# kb2040_pocketOperator_out_revA.net
KiCad netlist of a schematic drawn in EAGLE
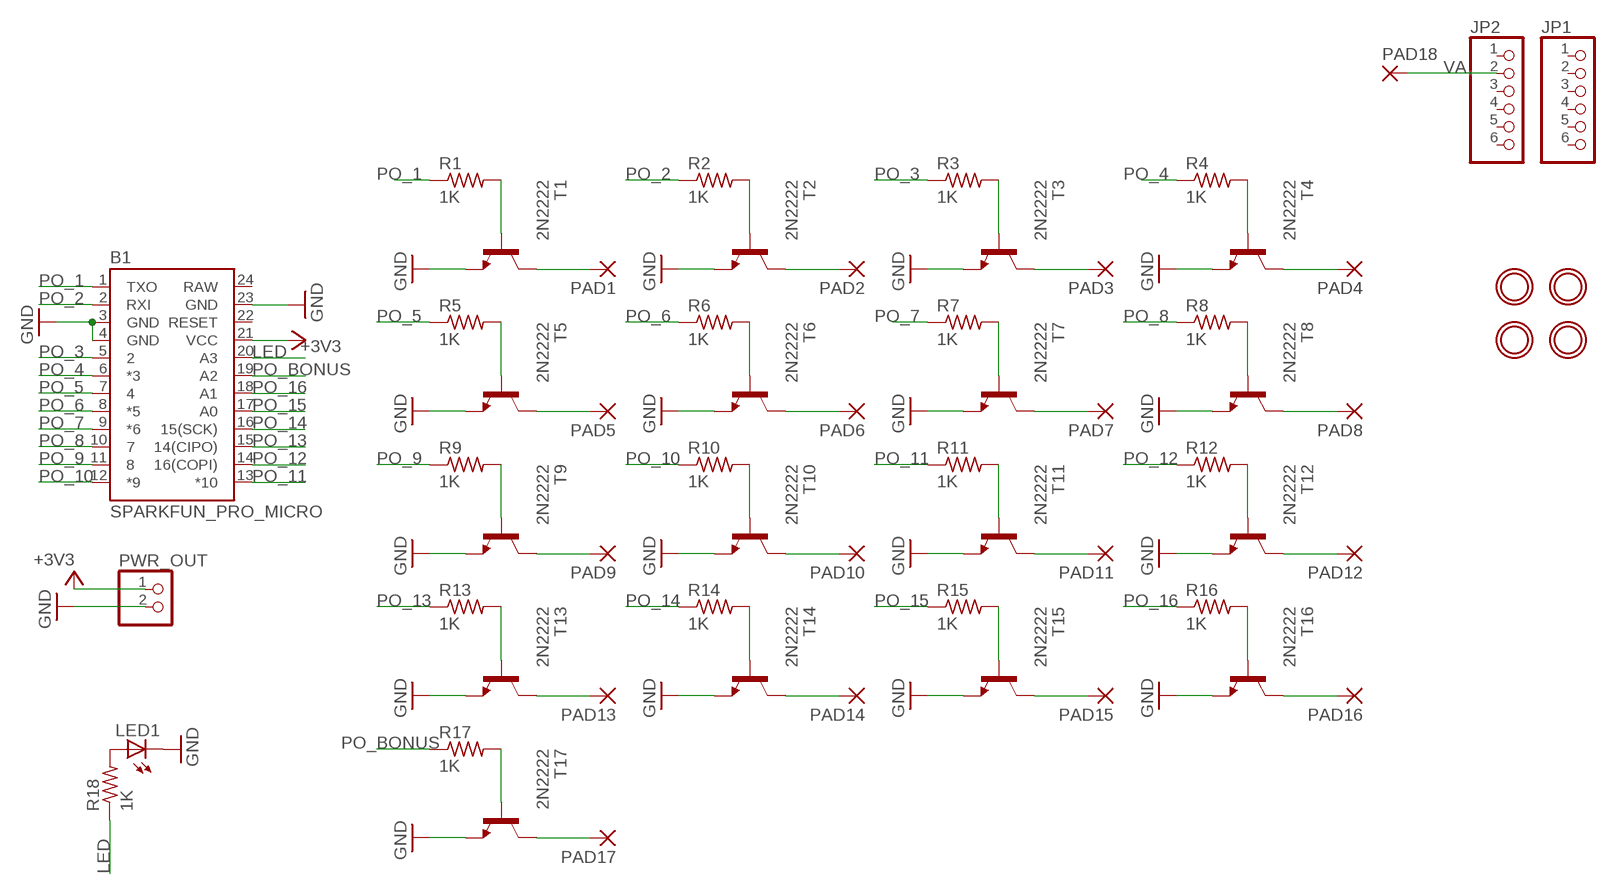
[diagram p0: schematic, sheet 1]

(export (version "E")
  (design (tool "Eeschema 10.0.6"))
  (components
    (comp (ref "B1")
      (value "SPARKFUN_PRO_MICRO")
      (footprint "eagle-import:SPARKFUN_PRO_MICRO")
      (libsource (lib "eagle-import") (part "SPARKFUN_PRO_MICRO"))
    )
    (comp (ref "JP1")
      (value "HEADER-1X670MIL")
      (footprint "eagle-import:1X06_ROUND_70")
      (libsource (lib "eagle-import") (part "HEADER-1X670MIL"))
    )
    (comp (ref "JP2")
      (value "HEADER-1X670MIL")
      (footprint "eagle-import:1X06_ROUND_70")
      (libsource (lib "eagle-import") (part "HEADER-1X670MIL"))
    )
    (comp (ref "LED1")
      (value "LED5MM")
      (footprint "eagle-import:LED5MM")
      (libsource (lib "eagle-import") (part "LED5MM"))
    )
    (comp (ref "PAD1")
      (value "2,54/1,1")
      (footprint "eagle-import:2,54_1,1")
      (libsource (lib "eagle-import") (part "2,54/1,1"))
    )
    (comp (ref "PAD2")
      (value "2,54/1,1")
      (footprint "eagle-import:2,54_1,1")
      (libsource (lib "eagle-import") (part "2,54/1,1"))
    )
    (comp (ref "PAD3")
      (value "2,54/1,1")
      (footprint "eagle-import:2,54_1,1")
      (libsource (lib "eagle-import") (part "2,54/1,1"))
    )
    (comp (ref "PAD4")
      (value "2,54/1,1")
      (footprint "eagle-import:2,54_1,1")
      (libsource (lib "eagle-import") (part "2,54/1,1"))
    )
    (comp (ref "PAD5")
      (value "2,54/1,1")
      (footprint "eagle-import:2,54_1,1")
      (libsource (lib "eagle-import") (part "2,54/1,1"))
    )
    (comp (ref "PAD6")
      (value "2,54/1,1")
      (footprint "eagle-import:2,54_1,1")
      (libsource (lib "eagle-import") (part "2,54/1,1"))
    )
    (comp (ref "PAD7")
      (value "2,54/1,1")
      (footprint "eagle-import:2,54_1,1")
      (libsource (lib "eagle-import") (part "2,54/1,1"))
    )
    (comp (ref "PAD8")
      (value "2,54/1,1")
      (footprint "eagle-import:2,54_1,1")
      (libsource (lib "eagle-import") (part "2,54/1,1"))
    )
    (comp (ref "PAD9")
      (value "2,54/1,1")
      (footprint "eagle-import:2,54_1,1")
      (libsource (lib "eagle-import") (part "2,54/1,1"))
    )
    (comp (ref "PAD10")
      (value "2,54/1,1")
      (footprint "eagle-import:2,54_1,1")
      (libsource (lib "eagle-import") (part "2,54/1,1"))
    )
    (comp (ref "PAD11")
      (value "2,54/1,1")
      (footprint "eagle-import:2,54_1,1")
      (libsource (lib "eagle-import") (part "2,54/1,1"))
    )
    (comp (ref "PAD12")
      (value "2,54/1,1")
      (footprint "eagle-import:2,54_1,1")
      (libsource (lib "eagle-import") (part "2,54/1,1"))
    )
    (comp (ref "PAD13")
      (value "2,54/1,1")
      (footprint "eagle-import:2,54_1,1")
      (libsource (lib "eagle-import") (part "2,54/1,1"))
    )
    (comp (ref "PAD14")
      (value "2,54/1,1")
      (footprint "eagle-import:2,54_1,1")
      (libsource (lib "eagle-import") (part "2,54/1,1"))
    )
    (comp (ref "PAD15")
      (value "2,54/1,1")
      (footprint "eagle-import:2,54_1,1")
      (libsource (lib "eagle-import") (part "2,54/1,1"))
    )
    (comp (ref "PAD16")
      (value "2,54/1,1")
      (footprint "eagle-import:2,54_1,1")
      (libsource (lib "eagle-import") (part "2,54/1,1"))
    )
    (comp (ref "PAD17")
      (value "2,54/1,1")
      (footprint "eagle-import:2,54_1,1")
      (libsource (lib "eagle-import") (part "2,54/1,1"))
    )
    (comp (ref "PAD18")
      (value "2,54/1,1")
      (footprint "eagle-import:2,54_1,1")
      (libsource (lib "eagle-import") (part "2,54/1,1"))
    )
    (comp (ref "PWR_OUT")
      (value "PINHD-1X2")
      (footprint "eagle-import:1X02")
      (libsource (lib "eagle-import") (part "PINHD-1X2"))
    )
    (comp (ref "R1")
      (value "1K")
      (footprint "eagle-import:0414V")
      (libsource (lib "eagle-import") (part "R-US_0414/5V"))
    )
    (comp (ref "R2")
      (value "1K")
      (footprint "eagle-import:0414V")
      (libsource (lib "eagle-import") (part "R-US_0414/5V"))
    )
    (comp (ref "R3")
      (value "1K")
      (footprint "eagle-import:0414V")
      (libsource (lib "eagle-import") (part "R-US_0414/5V"))
    )
    (comp (ref "R4")
      (value "1K")
      (footprint "eagle-import:0414V")
      (libsource (lib "eagle-import") (part "R-US_0414/5V"))
    )
    (comp (ref "R5")
      (value "1K")
      (footprint "eagle-import:0414V")
      (libsource (lib "eagle-import") (part "R-US_0414/5V"))
    )
    (comp (ref "R6")
      (value "1K")
      (footprint "eagle-import:0414V")
      (libsource (lib "eagle-import") (part "R-US_0414/5V"))
    )
    (comp (ref "R7")
      (value "1K")
      (footprint "eagle-import:0414V")
      (libsource (lib "eagle-import") (part "R-US_0414/5V"))
    )
    (comp (ref "R8")
      (value "1K")
      (footprint "eagle-import:0414V")
      (libsource (lib "eagle-import") (part "R-US_0414/5V"))
    )
    (comp (ref "R9")
      (value "1K")
      (footprint "eagle-import:0414V")
      (libsource (lib "eagle-import") (part "R-US_0414/5V"))
    )
    (comp (ref "R10")
      (value "1K")
      (footprint "eagle-import:0414V")
      (libsource (lib "eagle-import") (part "R-US_0414/5V"))
    )
    (comp (ref "R11")
      (value "1K")
      (footprint "eagle-import:0414V")
      (libsource (lib "eagle-import") (part "R-US_0414/5V"))
    )
    (comp (ref "R12")
      (value "1K")
      (footprint "eagle-import:0414V")
      (libsource (lib "eagle-import") (part "R-US_0414/5V"))
    )
    (comp (ref "R13")
      (value "1K")
      (footprint "eagle-import:0414V")
      (libsource (lib "eagle-import") (part "R-US_0414/5V"))
    )
    (comp (ref "R14")
      (value "1K")
      (footprint "eagle-import:0414V")
      (libsource (lib "eagle-import") (part "R-US_0414/5V"))
    )
    (comp (ref "R15")
      (value "1K")
      (footprint "eagle-import:0414V")
      (libsource (lib "eagle-import") (part "R-US_0414/5V"))
    )
    (comp (ref "R16")
      (value "1K")
      (footprint "eagle-import:0414V")
      (libsource (lib "eagle-import") (part "R-US_0414/5V"))
    )
    (comp (ref "R17")
      (value "1K")
      (footprint "eagle-import:0414V")
      (libsource (lib "eagle-import") (part "R-US_0414/5V"))
    )
    (comp (ref "R18")
      (value "1K")
      (footprint "eagle-import:0414V")
      (libsource (lib "eagle-import") (part "R-US_0414/5V"))
    )
    (comp (ref "T1")
      (value "2N2222")
      (footprint "eagle-import:TO92-EBC-OVAL")
      (libsource (lib "eagle-import") (part "2N2222"))
    )
    (comp (ref "T2")
      (value "2N2222")
      (footprint "eagle-import:TO92-EBC-OVAL")
      (libsource (lib "eagle-import") (part "2N2222"))
    )
    (comp (ref "T3")
      (value "2N2222")
      (footprint "eagle-import:TO92-EBC-OVAL")
      (libsource (lib "eagle-import") (part "2N2222"))
    )
    (comp (ref "T4")
      (value "2N2222")
      (footprint "eagle-import:TO92-EBC-OVAL")
      (libsource (lib "eagle-import") (part "2N2222"))
    )
    (comp (ref "T5")
      (value "2N2222")
      (footprint "eagle-import:TO92-EBC-OVAL")
      (libsource (lib "eagle-import") (part "2N2222"))
    )
    (comp (ref "T6")
      (value "2N2222")
      (footprint "eagle-import:TO92-EBC-OVAL")
      (libsource (lib "eagle-import") (part "2N2222"))
    )
    (comp (ref "T7")
      (value "2N2222")
      (footprint "eagle-import:TO92-EBC-OVAL")
      (libsource (lib "eagle-import") (part "2N2222"))
    )
    (comp (ref "T8")
      (value "2N2222")
      (footprint "eagle-import:TO92-EBC-OVAL")
      (libsource (lib "eagle-import") (part "2N2222"))
    )
    (comp (ref "T9")
      (value "2N2222")
      (footprint "eagle-import:TO92-EBC-OVAL")
      (libsource (lib "eagle-import") (part "2N2222"))
    )
    (comp (ref "T10")
      (value "2N2222")
      (footprint "eagle-import:TO92-EBC-OVAL")
      (libsource (lib "eagle-import") (part "2N2222"))
    )
    (comp (ref "T11")
      (value "2N2222")
      (footprint "eagle-import:TO92-EBC-OVAL")
      (libsource (lib "eagle-import") (part "2N2222"))
    )
    (comp (ref "T12")
      (value "2N2222")
      (footprint "eagle-import:TO92-EBC-OVAL")
      (libsource (lib "eagle-import") (part "2N2222"))
    )
    (comp (ref "T13")
      (value "2N2222")
      (footprint "eagle-import:TO92-EBC-OVAL")
      (libsource (lib "eagle-import") (part "2N2222"))
    )
    (comp (ref "T14")
      (value "2N2222")
      (footprint "eagle-import:TO92-EBC-OVAL")
      (libsource (lib "eagle-import") (part "2N2222"))
    )
    (comp (ref "T15")
      (value "2N2222")
      (footprint "eagle-import:TO92-EBC-OVAL")
      (libsource (lib "eagle-import") (part "2N2222"))
    )
    (comp (ref "T16")
      (value "2N2222")
      (footprint "eagle-import:TO92-EBC-OVAL")
      (libsource (lib "eagle-import") (part "2N2222"))
    )
    (comp (ref "T17")
      (value "2N2222")
      (footprint "eagle-import:TO92-EBC-OVAL")
      (libsource (lib "eagle-import") (part "2N2222"))
    )
    (comp (ref "U$1")
      (value "MOUNTINGHOLE2.5")
      (footprint "eagle-import:MOUNTINGHOLE_2.5_PLATED")
      (libsource (lib "eagle-import") (part "MOUNTINGHOLE2.5"))
    )
    (comp (ref "U$17")
      (value "MOUNTINGHOLE2.5")
      (footprint "eagle-import:MOUNTINGHOLE_2.5_PLATED")
      (libsource (lib "eagle-import") (part "MOUNTINGHOLE2.5"))
    )
    (comp (ref "U$19")
      (value "MOUNTINGHOLE2.5")
      (footprint "eagle-import:MOUNTINGHOLE_2.5_PLATED")
      (libsource (lib "eagle-import") (part "MOUNTINGHOLE2.5"))
    )
    (comp (ref "U$21")
      (value "MOUNTINGHOLE2.5")
      (footprint "eagle-import:MOUNTINGHOLE_2.5_PLATED")
      (libsource (lib "eagle-import") (part "MOUNTINGHOLE2.5"))
    )
  )
  (nets
    (net (code "1") (name "+3V3") (class "Default")
      (node (ref "B1") (pin "21") (pinfunction "VCC_21") (pintype "power_in"))
      (node (ref "PWR_OUT") (pin "1") (pinfunction "1_1") (pintype "passive"))
    )
    (net (code "2") (name "/LED") (class "Default")
      (node (ref "B1") (pin "20") (pinfunction "A3_20") (pintype "bidirectional"))
      (node (ref "R18") (pin "1") (pinfunction "1_1") (pintype "passive"))
    )
    (net (code "3") (name "/PO_1") (class "Default")
      (node (ref "B1") (pin "1") (pinfunction "TXO_1") (pintype "bidirectional"))
      (node (ref "R1") (pin "1") (pinfunction "1_1") (pintype "passive"))
    )
    (net (code "4") (name "/PO_2") (class "Default")
      (node (ref "B1") (pin "2") (pinfunction "RXI_2") (pintype "bidirectional"))
      (node (ref "R2") (pin "1") (pinfunction "1_1") (pintype "passive"))
    )
    (net (code "5") (name "/PO_3") (class "Default")
      (node (ref "B1") (pin "5") (pinfunction "2_5") (pintype "bidirectional"))
      (node (ref "R3") (pin "1") (pinfunction "1_1") (pintype "passive"))
    )
    (net (code "6") (name "/PO_4") (class "Default")
      (node (ref "B1") (pin "6") (pinfunction "*3_6") (pintype "bidirectional"))
      (node (ref "R4") (pin "1") (pinfunction "1_1") (pintype "passive"))
    )
    (net (code "7") (name "/PO_5") (class "Default")
      (node (ref "B1") (pin "7") (pinfunction "4_7") (pintype "bidirectional"))
      (node (ref "R5") (pin "1") (pinfunction "1_1") (pintype "passive"))
    )
    (net (code "8") (name "/PO_6") (class "Default")
      (node (ref "B1") (pin "8") (pinfunction "*5_8") (pintype "bidirectional"))
      (node (ref "R6") (pin "1") (pinfunction "1_1") (pintype "passive"))
    )
    (net (code "9") (name "/PO_7") (class "Default")
      (node (ref "B1") (pin "9") (pinfunction "*6_9") (pintype "bidirectional"))
      (node (ref "R7") (pin "1") (pinfunction "1_1") (pintype "passive"))
    )
    (net (code "10") (name "/PO_8") (class "Default")
      (node (ref "B1") (pin "10") (pinfunction "7_10") (pintype "bidirectional"))
      (node (ref "R8") (pin "1") (pinfunction "1_1") (pintype "passive"))
    )
    (net (code "11") (name "/PO_9") (class "Default")
      (node (ref "B1") (pin "11") (pinfunction "8_11") (pintype "bidirectional"))
      (node (ref "R9") (pin "1") (pinfunction "1_1") (pintype "passive"))
    )
    (net (code "12") (name "/PO_10") (class "Default")
      (node (ref "B1") (pin "12") (pinfunction "*9_12") (pintype "bidirectional"))
      (node (ref "R10") (pin "1") (pinfunction "1_1") (pintype "passive"))
    )
    (net (code "13") (name "/PO_11") (class "Default")
      (node (ref "B1") (pin "13") (pinfunction "*10_13") (pintype "bidirectional"))
      (node (ref "R11") (pin "1") (pinfunction "1_1") (pintype "passive"))
    )
    (net (code "14") (name "/PO_12") (class "Default")
      (node (ref "B1") (pin "14") (pinfunction "16(COPI)_14") (pintype "bidirectional"))
      (node (ref "R12") (pin "1") (pinfunction "1_1") (pintype "passive"))
    )
    (net (code "15") (name "/PO_13") (class "Default")
      (node (ref "B1") (pin "15") (pinfunction "14(CIPO)_15") (pintype "bidirectional"))
      (node (ref "R13") (pin "1") (pinfunction "1_1") (pintype "passive"))
    )
    (net (code "16") (name "/PO_14") (class "Default")
      (node (ref "B1") (pin "16") (pinfunction "15(SCK)_16") (pintype "bidirectional"))
      (node (ref "R14") (pin "1") (pinfunction "1_1") (pintype "passive"))
    )
    (net (code "17") (name "/PO_15") (class "Default")
      (node (ref "B1") (pin "17") (pinfunction "A0_17") (pintype "bidirectional"))
      (node (ref "R15") (pin "1") (pinfunction "1_1") (pintype "passive"))
    )
    (net (code "18") (name "/PO_16") (class "Default")
      (node (ref "B1") (pin "18") (pinfunction "A1_18") (pintype "bidirectional"))
      (node (ref "R16") (pin "1") (pinfunction "1_1") (pintype "passive"))
    )
    (net (code "19") (name "/PO_BONUS") (class "Default")
      (node (ref "B1") (pin "19") (pinfunction "A2_19") (pintype "bidirectional"))
      (node (ref "R17") (pin "1") (pinfunction "1_1") (pintype "passive"))
    )
    (net (code "20") (name "/RAW") (class "Default")
      (node (ref "B1") (pin "24") (pinfunction "RAW_24") (pintype "power_in"))
    )
    (net (code "21") (name "/VA") (class "Default")
      (node (ref "JP2") (pin "2") (pinfunction "2_2") (pintype "passive"))
      (node (ref "PAD18") (pin "1") (pinfunction "P_1") (pintype "passive"))
    )
    (net (code "22") (name "GND") (class "Default")
      (node (ref "B1") (pin "23") (pinfunction "GND_23") (pintype "power_in"))
      (node (ref "B1") (pin "3") (pinfunction "GND_3") (pintype "power_in"))
      (node (ref "B1") (pin "4") (pinfunction "GND_4") (pintype "power_in"))
      (node (ref "LED1") (pin "K") (pinfunction "C_K") (pintype "passive"))
      (node (ref "PWR_OUT") (pin "2") (pinfunction "2_2") (pintype "passive"))
      (node (ref "T1") (pin "E") (pinfunction "E_E") (pintype "passive"))
      (node (ref "T10") (pin "E") (pinfunction "E_E") (pintype "passive"))
      (node (ref "T11") (pin "E") (pinfunction "E_E") (pintype "passive"))
      (node (ref "T12") (pin "E") (pinfunction "E_E") (pintype "passive"))
      (node (ref "T13") (pin "E") (pinfunction "E_E") (pintype "passive"))
      (node (ref "T14") (pin "E") (pinfunction "E_E") (pintype "passive"))
      (node (ref "T15") (pin "E") (pinfunction "E_E") (pintype "passive"))
      (node (ref "T16") (pin "E") (pinfunction "E_E") (pintype "passive"))
      (node (ref "T17") (pin "E") (pinfunction "E_E") (pintype "passive"))
      (node (ref "T2") (pin "E") (pinfunction "E_E") (pintype "passive"))
      (node (ref "T3") (pin "E") (pinfunction "E_E") (pintype "passive"))
      (node (ref "T4") (pin "E") (pinfunction "E_E") (pintype "passive"))
      (node (ref "T5") (pin "E") (pinfunction "E_E") (pintype "passive"))
      (node (ref "T6") (pin "E") (pinfunction "E_E") (pintype "passive"))
      (node (ref "T7") (pin "E") (pinfunction "E_E") (pintype "passive"))
      (node (ref "T8") (pin "E") (pinfunction "E_E") (pintype "passive"))
      (node (ref "T9") (pin "E") (pinfunction "E_E") (pintype "passive"))
    )
    (net (code "23") (name "Net-(LED1-PadA)") (class "Default")
      (node (ref "LED1") (pin "A") (pinfunction "A_A") (pintype "passive"))
      (node (ref "R18") (pin "2") (pinfunction "2_2") (pintype "passive"))
    )
    (net (code "24") (name "Net-(PAD1-P)") (class "Default")
      (node (ref "PAD1") (pin "1") (pinfunction "P_1") (pintype "passive"))
      (node (ref "T1") (pin "C") (pinfunction "C_C") (pintype "passive"))
    )
    (net (code "25") (name "Net-(PAD2-P)") (class "Default")
      (node (ref "PAD2") (pin "1") (pinfunction "P_1") (pintype "passive"))
      (node (ref "T2") (pin "C") (pinfunction "C_C") (pintype "passive"))
    )
    (net (code "26") (name "Net-(PAD3-P)") (class "Default")
      (node (ref "PAD3") (pin "1") (pinfunction "P_1") (pintype "passive"))
      (node (ref "T3") (pin "C") (pinfunction "C_C") (pintype "passive"))
    )
    (net (code "27") (name "Net-(PAD4-P)") (class "Default")
      (node (ref "PAD4") (pin "1") (pinfunction "P_1") (pintype "passive"))
      (node (ref "T4") (pin "C") (pinfunction "C_C") (pintype "passive"))
    )
    (net (code "28") (name "Net-(PAD5-P)") (class "Default")
      (node (ref "PAD5") (pin "1") (pinfunction "P_1") (pintype "passive"))
      (node (ref "T5") (pin "C") (pinfunction "C_C") (pintype "passive"))
    )
    (net (code "29") (name "Net-(PAD6-P)") (class "Default")
      (node (ref "PAD6") (pin "1") (pinfunction "P_1") (pintype "passive"))
      (node (ref "T6") (pin "C") (pinfunction "C_C") (pintype "passive"))
    )
    (net (code "30") (name "Net-(PAD7-P)") (class "Default")
      (node (ref "PAD7") (pin "1") (pinfunction "P_1") (pintype "passive"))
      (node (ref "T7") (pin "C") (pinfunction "C_C") (pintype "passive"))
    )
    (net (code "31") (name "Net-(PAD8-P)") (class "Default")
      (node (ref "PAD8") (pin "1") (pinfunction "P_1") (pintype "passive"))
      (node (ref "T8") (pin "C") (pinfunction "C_C") (pintype "passive"))
    )
    (net (code "32") (name "Net-(PAD9-P)") (class "Default")
      (node (ref "PAD9") (pin "1") (pinfunction "P_1") (pintype "passive"))
      (node (ref "T9") (pin "C") (pinfunction "C_C") (pintype "passive"))
    )
    (net (code "33") (name "Net-(PAD10-P)") (class "Default")
      (node (ref "PAD10") (pin "1") (pinfunction "P_1") (pintype "passive"))
      (node (ref "T10") (pin "C") (pinfunction "C_C") (pintype "passive"))
    )
    (net (code "34") (name "Net-(PAD11-P)") (class "Default")
      (node (ref "PAD11") (pin "1") (pinfunction "P_1") (pintype "passive"))
      (node (ref "T11") (pin "C") (pinfunction "C_C") (pintype "passive"))
    )
    (net (code "35") (name "Net-(PAD12-P)") (class "Default")
      (node (ref "PAD12") (pin "1") (pinfunction "P_1") (pintype "passive"))
      (node (ref "T12") (pin "C") (pinfunction "C_C") (pintype "passive"))
    )
    (net (code "36") (name "Net-(PAD13-P)") (class "Default")
      (node (ref "PAD13") (pin "1") (pinfunction "P_1") (pintype "passive"))
      (node (ref "T13") (pin "C") (pinfunction "C_C") (pintype "passive"))
    )
    (net (code "37") (name "Net-(PAD14-P)") (class "Default")
      (node (ref "PAD14") (pin "1") (pinfunction "P_1") (pintype "passive"))
      (node (ref "T14") (pin "C") (pinfunction "C_C") (pintype "passive"))
    )
    (net (code "38") (name "Net-(PAD15-P)") (class "Default")
      (node (ref "PAD15") (pin "1") (pinfunction "P_1") (pintype "passive"))
      (node (ref "T15") (pin "C") (pinfunction "C_C") (pintype "passive"))
    )
    (net (code "39") (name "Net-(PAD16-P)") (class "Default")
      (node (ref "PAD16") (pin "1") (pinfunction "P_1") (pintype "passive"))
      (node (ref "T16") (pin "C") (pinfunction "C_C") (pintype "passive"))
    )
    (net (code "40") (name "Net-(PAD17-P)") (class "Default")
      (node (ref "PAD17") (pin "1") (pinfunction "P_1") (pintype "passive"))
      (node (ref "T17") (pin "C") (pinfunction "C_C") (pintype "passive"))
    )
    (net (code "41") (name "Net-(R1-Pad2)") (class "Default")
      (node (ref "R1") (pin "2") (pinfunction "2_2") (pintype "passive"))
      (node (ref "T1") (pin "B") (pinfunction "B_B") (pintype "passive"))
    )
    (net (code "42") (name "Net-(R2-Pad2)") (class "Default")
      (node (ref "R2") (pin "2") (pinfunction "2_2") (pintype "passive"))
      (node (ref "T2") (pin "B") (pinfunction "B_B") (pintype "passive"))
    )
    (net (code "43") (name "Net-(R3-Pad2)") (class "Default")
      (node (ref "R3") (pin "2") (pinfunction "2_2") (pintype "passive"))
      (node (ref "T3") (pin "B") (pinfunction "B_B") (pintype "passive"))
    )
    (net (code "44") (name "Net-(R4-Pad2)") (class "Default")
      (node (ref "R4") (pin "2") (pinfunction "2_2") (pintype "passive"))
      (node (ref "T4") (pin "B") (pinfunction "B_B") (pintype "passive"))
    )
    (net (code "45") (name "Net-(R5-Pad2)") (class "Default")
      (node (ref "R5") (pin "2") (pinfunction "2_2") (pintype "passive"))
      (node (ref "T5") (pin "B") (pinfunction "B_B") (pintype "passive"))
    )
    (net (code "46") (name "Net-(R6-Pad2)") (class "Default")
      (node (ref "R6") (pin "2") (pinfunction "2_2") (pintype "passive"))
      (node (ref "T6") (pin "B") (pinfunction "B_B") (pintype "passive"))
    )
    (net (code "47") (name "Net-(R7-Pad2)") (class "Default")
      (node (ref "R7") (pin "2") (pinfunction "2_2") (pintype "passive"))
      (node (ref "T7") (pin "B") (pinfunction "B_B") (pintype "passive"))
    )
    (net (code "48") (name "Net-(R8-Pad2)") (class "Default")
      (node (ref "R8") (pin "2") (pinfunction "2_2") (pintype "passive"))
      (node (ref "T8") (pin "B") (pinfunction "B_B") (pintype "passive"))
    )
    (net (code "49") (name "Net-(R9-Pad2)") (class "Default")
      (node (ref "R9") (pin "2") (pinfunction "2_2") (pintype "passive"))
      (node (ref "T9") (pin "B") (pinfunction "B_B") (pintype "passive"))
    )
    (net (code "50") (name "Net-(R10-Pad2)") (class "Default")
      (node (ref "R10") (pin "2") (pinfunction "2_2") (pintype "passive"))
      (node (ref "T10") (pin "B") (pinfunction "B_B") (pintype "passive"))
    )
    (net (code "51") (name "Net-(R11-Pad2)") (class "Default")
      (node (ref "R11") (pin "2") (pinfunction "2_2") (pintype "passive"))
      (node (ref "T11") (pin "B") (pinfunction "B_B") (pintype "passive"))
    )
    (net (code "52") (name "Net-(R12-Pad2)") (class "Default")
      (node (ref "R12") (pin "2") (pinfunction "2_2") (pintype "passive"))
      (node (ref "T12") (pin "B") (pinfunction "B_B") (pintype "passive"))
    )
    (net (code "53") (name "Net-(R13-Pad2)") (class "Default")
      (node (ref "R13") (pin "2") (pinfunction "2_2") (pintype "passive"))
      (node (ref "T13") (pin "B") (pinfunction "B_B") (pintype "passive"))
    )
    (net (code "54") (name "Net-(R14-Pad2)") (class "Default")
      (node (ref "R14") (pin "2") (pinfunction "2_2") (pintype "passive"))
      (node (ref "T14") (pin "B") (pinfunction "B_B") (pintype "passive"))
    )
    (net (code "55") (name "Net-(R15-Pad2)") (class "Default")
      (node (ref "R15") (pin "2") (pinfunction "2_2") (pintype "passive"))
      (node (ref "T15") (pin "B") (pinfunction "B_B") (pintype "passive"))
    )
    (net (code "56") (name "Net-(R16-Pad2)") (class "Default")
      (node (ref "R16") (pin "2") (pinfunction "2_2") (pintype "passive"))
      (node (ref "T16") (pin "B") (pinfunction "B_B") (pintype "passive"))
    )
    (net (code "57") (name "Net-(R17-Pad2)") (class "Default")
      (node (ref "R17") (pin "2") (pinfunction "2_2") (pintype "passive"))
      (node (ref "T17") (pin "B") (pinfunction "B_B") (pintype "passive"))
    )
    (net (code "58") (name "unconnected-(B1-RESET-Pad22)") (class "Default")
      (node (ref "B1") (pin "22") (pinfunction "RESET_22") (pintype "bidirectional"))
    )
    (net (code "59") (name "unconnected-(JP1-Pad1)") (class "Default")
      (node (ref "JP1") (pin "1") (pinfunction "1_1") (pintype "passive"))
    )
    (net (code "60") (name "unconnected-(JP1-Pad2)") (class "Default")
      (node (ref "JP1") (pin "2") (pinfunction "2_2") (pintype "passive"))
    )
    (net (code "61") (name "unconnected-(JP1-Pad3)") (class "Default")
      (node (ref "JP1") (pin "3") (pinfunction "3_3") (pintype "passive"))
    )
    (net (code "62") (name "unconnected-(JP1-Pad4)") (class "Default")
      (node (ref "JP1") (pin "4") (pinfunction "4_4") (pintype "passive"))
    )
    (net (code "63") (name "unconnected-(JP1-Pad5)") (class "Default")
      (node (ref "JP1") (pin "5") (pinfunction "5_5") (pintype "passive"))
    )
    (net (code "64") (name "unconnected-(JP1-Pad6)") (class "Default")
      (node (ref "JP1") (pin "6") (pinfunction "6_6") (pintype "passive"))
    )
    (net (code "65") (name "unconnected-(JP2-Pad1)") (class "Default")
      (node (ref "JP2") (pin "1") (pinfunction "1_1") (pintype "passive"))
    )
    (net (code "66") (name "unconnected-(JP2-Pad3)") (class "Default")
      (node (ref "JP2") (pin "3") (pinfunction "3_3") (pintype "passive"))
    )
    (net (code "67") (name "unconnected-(JP2-Pad4)") (class "Default")
      (node (ref "JP2") (pin "4") (pinfunction "4_4") (pintype "passive"))
    )
    (net (code "68") (name "unconnected-(JP2-Pad5)") (class "Default")
      (node (ref "JP2") (pin "5") (pinfunction "5_5") (pintype "passive"))
    )
    (net (code "69") (name "unconnected-(JP2-Pad6)") (class "Default")
      (node (ref "JP2") (pin "6") (pinfunction "6_6") (pintype "passive"))
    )
  )
)
